# hackeeg-connector-8.net
KiCad netlist of a schematic drawn in EAGLE
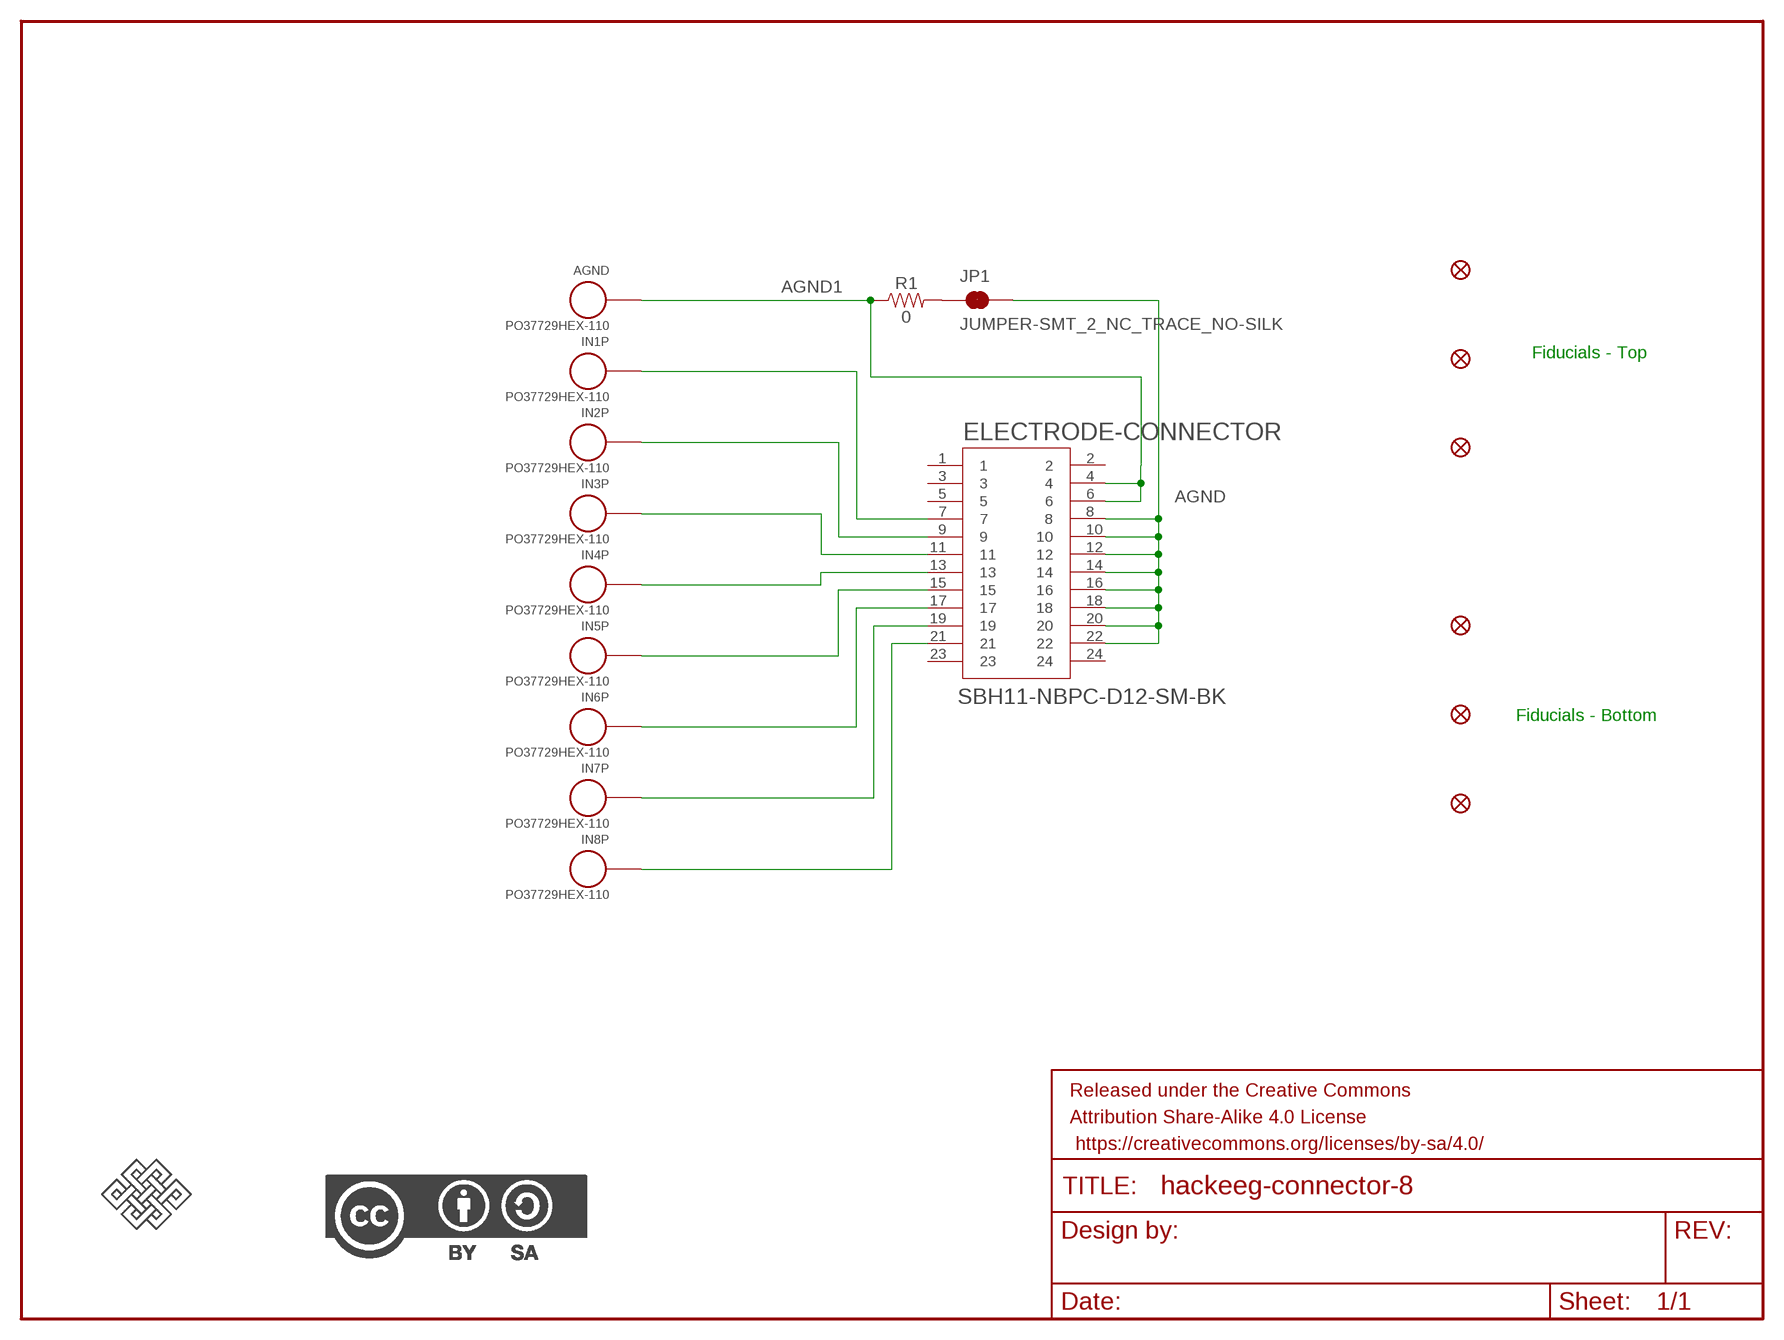
[diagram p0: schematic, sheet 1]

(export (version "E")
  (design (tool "Eeschema 10.0.6"))
  (components
    (comp (ref "AGND")
      (value "PO37729HEX-110")
      (footprint "eagle-import:HEX-110")
      (libsource (lib "eagle-import") (part "PO37729HEX-110"))
    )
    (comp (ref "ELECTRODE-CONNECTOR")
      (value "SBH11-NBPC-D12-SM-BK")
      (footprint "eagle-import:SULLINS_SBH11-NBPC-D12-SM-BK")
      (fields (field (name "MF") "Sullins Connector"))
      (libsource (lib "eagle-import") (part "SBH11-NBPC-D12-SM-BK"))
    )
    (comp (ref "FD1")
      (value "FIDUCIAL1X2")
      (footprint "eagle-import:FIDUCIAL-1X2")
      (libsource (lib "eagle-import") (part "FIDUCIAL1X2"))
    )
    (comp (ref "FD2")
      (value "FIDUCIAL1X2")
      (footprint "eagle-import:FIDUCIAL-1X2")
      (libsource (lib "eagle-import") (part "FIDUCIAL1X2"))
    )
    (comp (ref "FD3")
      (value "FIDUCIAL1X2")
      (footprint "eagle-import:FIDUCIAL-1X2")
      (libsource (lib "eagle-import") (part "FIDUCIAL1X2"))
    )
    (comp (ref "FD4")
      (value "FIDUCIAL1X2")
      (footprint "eagle-import:FIDUCIAL-1X2")
      (libsource (lib "eagle-import") (part "FIDUCIAL1X2"))
    )
    (comp (ref "FD5")
      (value "FIDUCIAL1X2")
      (footprint "eagle-import:FIDUCIAL-1X2")
      (libsource (lib "eagle-import") (part "FIDUCIAL1X2"))
    )
    (comp (ref "FD6")
      (value "FIDUCIAL1X2")
      (footprint "eagle-import:FIDUCIAL-1X2")
      (libsource (lib "eagle-import") (part "FIDUCIAL1X2"))
    )
    (comp (ref "FRAME1")
      (value "FRAME-LETTER")
      (footprint "eagle-import:CREATIVE_COMMONS")
      (libsource (lib "eagle-import") (part "FRAME-LETTER"))
    )
    (comp (ref "IN1P")
      (value "PO37729HEX-110")
      (footprint "eagle-import:HEX-110")
      (libsource (lib "eagle-import") (part "PO37729HEX-110"))
    )
    (comp (ref "IN2P")
      (value "PO37729HEX-110")
      (footprint "eagle-import:HEX-110")
      (libsource (lib "eagle-import") (part "PO37729HEX-110"))
    )
    (comp (ref "IN3P")
      (value "PO37729HEX-110")
      (footprint "eagle-import:HEX-110")
      (libsource (lib "eagle-import") (part "PO37729HEX-110"))
    )
    (comp (ref "IN4P")
      (value "PO37729HEX-110")
      (footprint "eagle-import:HEX-110")
      (libsource (lib "eagle-import") (part "PO37729HEX-110"))
    )
    (comp (ref "IN5P")
      (value "PO37729HEX-110")
      (footprint "eagle-import:HEX-110")
      (libsource (lib "eagle-import") (part "PO37729HEX-110"))
    )
    (comp (ref "IN6P")
      (value "PO37729HEX-110")
      (footprint "eagle-import:HEX-110")
      (libsource (lib "eagle-import") (part "PO37729HEX-110"))
    )
    (comp (ref "IN7P")
      (value "PO37729HEX-110")
      (footprint "eagle-import:HEX-110")
      (libsource (lib "eagle-import") (part "PO37729HEX-110"))
    )
    (comp (ref "IN8P")
      (value "PO37729HEX-110")
      (footprint "eagle-import:HEX-110")
      (libsource (lib "eagle-import") (part "PO37729HEX-110"))
    )
    (comp (ref "JP1")
      (value "JUMPER-SMT_2_NC_TRACE_NO-SILK")
      (footprint "eagle-import:SMT-JUMPER_2_NC_TRACE_NO-SILK")
      (libsource (lib "eagle-import") (part "JUMPER-SMT_2_NC_TRACE_NO-SILK"))
    )
    (comp (ref "R1")
      (value "0")
      (footprint "eagle-import:0603")
      (libsource (lib "eagle-import") (part "0OHM-0603-1/10W-5%"))
    )
    (comp (ref "U$1")
      (value "ENDLESSKNOTENDLESSKNOT-MEDIUM")
      (footprint "eagle-import:ENDLESSKNOT-MEDIUM")
      (libsource (lib "eagle-import") (part "ENDLESSKNOTENDLESSKNOT-MEDIUM"))
    )
    (comp (ref "U$13")
      (value "CC-BY-SA")
      (footprint "eagle-import:CC-BY-SA")
      (libsource (lib "eagle-import") (part "CC-BY-SA"))
    )
  )
  (nets
    (net (code "1") (name "/AGND") (class "Default")
      (node (ref "ELECTRODE-CONNECTOR") (pin "10") (pinfunction "10_10") (pintype "passive"))
      (node (ref "ELECTRODE-CONNECTOR") (pin "12") (pinfunction "12_12") (pintype "passive"))
      (node (ref "ELECTRODE-CONNECTOR") (pin "14") (pinfunction "14_14") (pintype "passive"))
      (node (ref "ELECTRODE-CONNECTOR") (pin "16") (pinfunction "16_16") (pintype "passive"))
      (node (ref "ELECTRODE-CONNECTOR") (pin "18") (pinfunction "18_18") (pintype "passive"))
      (node (ref "ELECTRODE-CONNECTOR") (pin "20") (pinfunction "20_20") (pintype "passive"))
      (node (ref "ELECTRODE-CONNECTOR") (pin "22") (pinfunction "22_22") (pintype "passive"))
      (node (ref "ELECTRODE-CONNECTOR") (pin "8") (pinfunction "8_8") (pintype "passive"))
      (node (ref "JP1") (pin "2") (pinfunction "2_2") (pintype "passive"))
    )
    (net (code "2") (name "/AGND1") (class "Default")
      (node (ref "AGND") (pin "SIGNAL") (pinfunction "SIGNAL_SIGNAL") (pintype "bidirectional"))
      (node (ref "ELECTRODE-CONNECTOR") (pin "4") (pinfunction "4_4") (pintype "passive"))
      (node (ref "ELECTRODE-CONNECTOR") (pin "6") (pinfunction "6_6") (pintype "passive"))
      (node (ref "R1") (pin "1") (pinfunction "1_1") (pintype "passive"))
    )
    (net (code "3") (name "Net-(ELECTRODE-CONNECTOR-Pad7)") (class "Default")
      (node (ref "ELECTRODE-CONNECTOR") (pin "7") (pinfunction "7_7") (pintype "passive"))
      (node (ref "IN1P") (pin "SIGNAL") (pinfunction "SIGNAL_SIGNAL") (pintype "bidirectional"))
    )
    (net (code "4") (name "Net-(ELECTRODE-CONNECTOR-Pad9)") (class "Default")
      (node (ref "ELECTRODE-CONNECTOR") (pin "9") (pinfunction "9_9") (pintype "passive"))
      (node (ref "IN2P") (pin "SIGNAL") (pinfunction "SIGNAL_SIGNAL") (pintype "bidirectional"))
    )
    (net (code "5") (name "Net-(ELECTRODE-CONNECTOR-Pad11)") (class "Default")
      (node (ref "ELECTRODE-CONNECTOR") (pin "11") (pinfunction "11_11") (pintype "passive"))
      (node (ref "IN3P") (pin "SIGNAL") (pinfunction "SIGNAL_SIGNAL") (pintype "bidirectional"))
    )
    (net (code "6") (name "Net-(ELECTRODE-CONNECTOR-Pad13)") (class "Default")
      (node (ref "ELECTRODE-CONNECTOR") (pin "13") (pinfunction "13_13") (pintype "passive"))
      (node (ref "IN4P") (pin "SIGNAL") (pinfunction "SIGNAL_SIGNAL") (pintype "bidirectional"))
    )
    (net (code "7") (name "Net-(ELECTRODE-CONNECTOR-Pad15)") (class "Default")
      (node (ref "ELECTRODE-CONNECTOR") (pin "15") (pinfunction "15_15") (pintype "passive"))
      (node (ref "IN5P") (pin "SIGNAL") (pinfunction "SIGNAL_SIGNAL") (pintype "bidirectional"))
    )
    (net (code "8") (name "Net-(ELECTRODE-CONNECTOR-Pad17)") (class "Default")
      (node (ref "ELECTRODE-CONNECTOR") (pin "17") (pinfunction "17_17") (pintype "passive"))
      (node (ref "IN6P") (pin "SIGNAL") (pinfunction "SIGNAL_SIGNAL") (pintype "bidirectional"))
    )
    (net (code "9") (name "Net-(ELECTRODE-CONNECTOR-Pad19)") (class "Default")
      (node (ref "ELECTRODE-CONNECTOR") (pin "19") (pinfunction "19_19") (pintype "passive"))
      (node (ref "IN7P") (pin "SIGNAL") (pinfunction "SIGNAL_SIGNAL") (pintype "bidirectional"))
    )
    (net (code "10") (name "Net-(ELECTRODE-CONNECTOR-Pad21)") (class "Default")
      (node (ref "ELECTRODE-CONNECTOR") (pin "21") (pinfunction "21_21") (pintype "passive"))
      (node (ref "IN8P") (pin "SIGNAL") (pinfunction "SIGNAL_SIGNAL") (pintype "bidirectional"))
    )
    (net (code "11") (name "Net-(JP1-Pad1)") (class "Default")
      (node (ref "JP1") (pin "1") (pinfunction "1_1") (pintype "passive"))
      (node (ref "R1") (pin "2") (pinfunction "2_2") (pintype "passive"))
    )
    (net (code "12") (name "unconnected-(ELECTRODE-CONNECTOR-Pad1)") (class "Default")
      (node (ref "ELECTRODE-CONNECTOR") (pin "1") (pinfunction "1_1") (pintype "passive"))
    )
    (net (code "13") (name "unconnected-(ELECTRODE-CONNECTOR-Pad2)") (class "Default")
      (node (ref "ELECTRODE-CONNECTOR") (pin "2") (pinfunction "2_2") (pintype "passive"))
    )
    (net (code "14") (name "unconnected-(ELECTRODE-CONNECTOR-Pad3)") (class "Default")
      (node (ref "ELECTRODE-CONNECTOR") (pin "3") (pinfunction "3_3") (pintype "passive"))
    )
    (net (code "15") (name "unconnected-(ELECTRODE-CONNECTOR-Pad5)") (class "Default")
      (node (ref "ELECTRODE-CONNECTOR") (pin "5") (pinfunction "5_5") (pintype "passive"))
    )
    (net (code "16") (name "unconnected-(ELECTRODE-CONNECTOR-Pad23)") (class "Default")
      (node (ref "ELECTRODE-CONNECTOR") (pin "23") (pinfunction "23_23") (pintype "passive"))
    )
    (net (code "17") (name "unconnected-(ELECTRODE-CONNECTOR-Pad24)") (class "Default")
      (node (ref "ELECTRODE-CONNECTOR") (pin "24") (pinfunction "24_24") (pintype "passive"))
    )
  )
)
